# GPS_supply2.net
KiCad netlist of a schematic drawn in Altium Designer
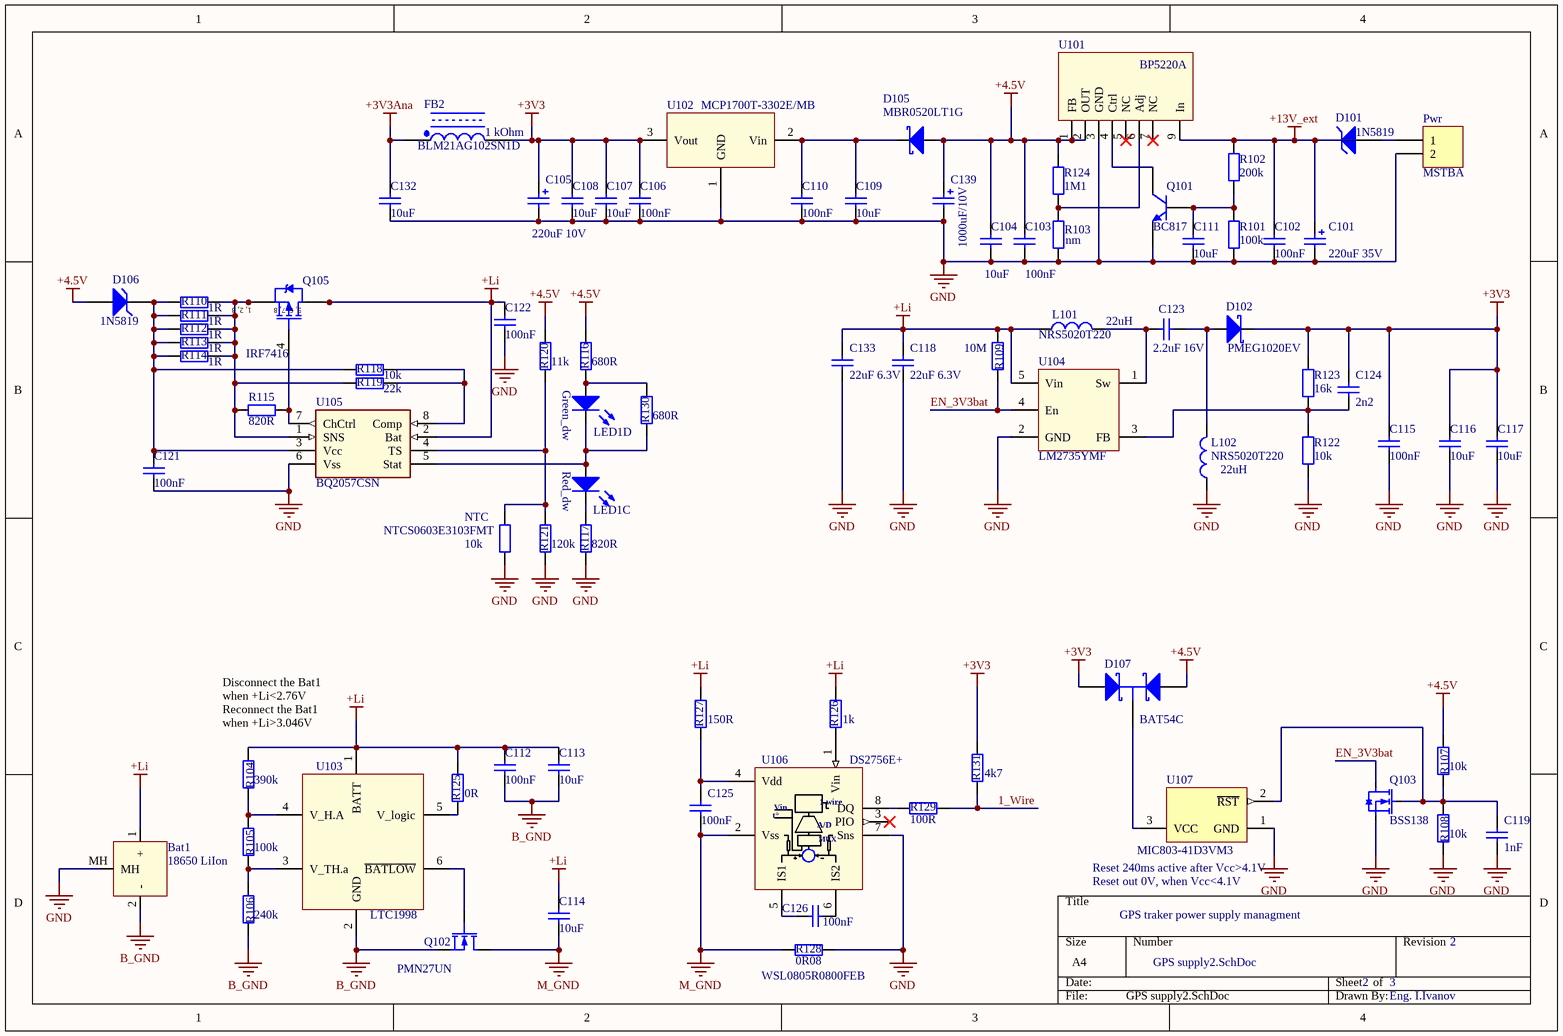
[diagram p0: GPS supply2.SchDoc]

(export (version "E")
  (design (tool "Eeschema 10.0.6"))
  (components
    (comp (ref "Bat1")
      (value "18650 LiIon")
      (footprint "18650")
      (description "18650 cell")
      (fields (field (name "Comment") "LiIon") (field (name "CREATED") "charge"))
      (libsource (lib "ANG_6VA transformers") (part "LiIon"))
    )
    (comp (ref "C101")
      (value "220uF 35V")
      (footprint "Cap electrolyt 7")
      (description "Polarized Capacitor (TH)")
      (fields (field (name "PUBLISHER") "Altium Limited"))
      (libsource (lib "Electolyt Caps") (part "CAP ELECTOLYT"))
    )
    (comp (ref "C102")
      (value "100nF")
      (footprint "2012[0805]")
      (description "Capacitor (Semiconductor SIM Model)")
      (fields (field (name "Comment") "Cap Semi") (field (name "PUBLISHER") "Altium Limited"))
      (libsource (lib "altium-import") (part "root_1_Cap Semi_"))
    )
    (comp (ref "C103")
      (value "100nF")
      (footprint "2012[0805]")
      (description "Capacitor (Semiconductor SIM Model)")
      (fields (field (name "Comment") "Cap Semi") (field (name "PUBLISHER") "Altium Limited"))
      (libsource (lib "Miscellaneous Devices") (part "Cap Semi"))
    )
    (comp (ref "C104")
      (value "10uF")
      (footprint "2012[0805]")
      (description "Capacitor (Semiconductor SIM Model)")
      (fields (field (name "Comment") "Cap Semi") (field (name "PUBLISHER") "Altium Limited"))
      (libsource (lib "Miscellaneous Devices") (part "Cap Semi"))
    )
    (comp (ref "C105")
      (value "220uF 10V")
      (footprint "Cap electrolyt 8")
      (description "Polarized Capacitor (TH)")
      (fields (field (name "Comment") "CAP ELECTOLYT") (field (name "PUBLISHER") "Altium Limited"))
      (libsource (lib "Electolyt Caps") (part "CAP ELECTOLYT"))
    )
    (comp (ref "C106")
      (value "100nF")
      (footprint "2012[0805]")
      (description "Capacitor (Semiconductor SIM Model)")
      (fields (field (name "Comment") "Cap Semi") (field (name "PUBLISHER") "Altium Limited"))
      (libsource (lib "Miscellaneous Devices") (part "Cap Semi"))
    )
    (comp (ref "C107")
      (value "10uF")
      (footprint "2012[0805]")
      (description "Capacitor (Semiconductor SIM Model)")
      (fields (field (name "Comment") "Cap Semi") (field (name "PUBLISHER") "Altium Limited"))
      (libsource (lib "Miscellaneous Devices") (part "Cap Semi"))
    )
    (comp (ref "C108")
      (value "10uF")
      (footprint "2012[0805]")
      (description "Capacitor (Semiconductor SIM Model)")
      (fields (field (name "Comment") "Cap Semi") (field (name "PUBLISHER") "Altium Limited"))
      (libsource (lib "Miscellaneous Devices") (part "Cap Semi"))
    )
    (comp (ref "C109")
      (value "10uF")
      (footprint "2012[0805]")
      (description "Capacitor (Semiconductor SIM Model)")
      (fields (field (name "Comment") "Cap Semi") (field (name "PUBLISHER") "Altium Limited"))
      (libsource (lib "Miscellaneous Devices") (part "Cap Semi"))
    )
    (comp (ref "C110")
      (value "100nF")
      (footprint "2012[0805]")
      (description "Capacitor (Semiconductor SIM Model)")
      (fields (field (name "Comment") "Cap Semi") (field (name "PUBLISHER") "Altium Limited"))
      (libsource (lib "Miscellaneous Devices") (part "Cap Semi"))
    )
    (comp (ref "C111")
      (value "10uF")
      (footprint "2012[0805]")
      (description "Capacitor (Semiconductor SIM Model)")
      (fields (field (name "Comment") "Cap Semi") (field (name "PUBLISHER") "Altium Limited"))
      (libsource (lib "Miscellaneous Devices") (part "Cap Semi"))
    )
    (comp (ref "C112")
      (value "100nF")
      (footprint "2012[0805]")
      (description "Capacitor (Semiconductor SIM Model)")
      (fields (field (name "Comment") "Cap Semi") (field (name "PUBLISHER") "Altium Limited"))
      (libsource (lib "Miscellaneous Devices") (part "Cap Semi"))
    )
    (comp (ref "C113")
      (value "10uF")
      (footprint "2012[0805]")
      (description "Capacitor (Semiconductor SIM Model)")
      (fields (field (name "Comment") "Cap Semi") (field (name "PUBLISHER") "Altium Limited"))
      (libsource (lib "Miscellaneous Devices") (part "Cap Semi"))
    )
    (comp (ref "C114")
      (value "10uF")
      (footprint "2012[0805]")
      (description "Capacitor (Semiconductor SIM Model)")
      (fields (field (name "Comment") "Cap Semi") (field (name "PUBLISHER") "Altium Limited"))
      (libsource (lib "Miscellaneous Devices") (part "Cap Semi"))
    )
    (comp (ref "C115")
      (value "100nF")
      (footprint "2012[0805]")
      (description "Capacitor (Semiconductor SIM Model)")
      (fields (field (name "Comment") "Cap Semi") (field (name "PUBLISHER") "Altium Limited"))
      (libsource (lib "Miscellaneous Devices") (part "Cap Semi"))
    )
    (comp (ref "C116")
      (value "10uF")
      (footprint "2012[0805]")
      (description "Capacitor (Semiconductor SIM Model)")
      (fields (field (name "Comment") "Cap Semi") (field (name "PUBLISHER") "Altium Limited"))
      (libsource (lib "Miscellaneous Devices") (part "Cap Semi"))
    )
    (comp (ref "C117")
      (value "10uF")
      (footprint "2012[0805]")
      (description "Capacitor (Semiconductor SIM Model)")
      (fields (field (name "Comment") "Cap Semi") (field (name "PUBLISHER") "Altium Limited"))
      (libsource (lib "Miscellaneous Devices") (part "Cap Semi"))
    )
    (comp (ref "C118")
      (value "22uF 6.3V")
      (footprint "2012[0805]")
      (description "Capacitor (Semiconductor SIM Model)")
      (fields (field (name "Comment") "Cap Semi") (field (name "PUBLISHER") "Altium Limited"))
      (libsource (lib "Miscellaneous Devices") (part "Cap Semi"))
    )
    (comp (ref "C119")
      (value "1nF")
      (footprint "2012[0805]")
      (description "Capacitor (Semiconductor SIM Model)")
      (fields (field (name "Comment") "Cap Semi") (field (name "PUBLISHER") "Altium Limited"))
      (libsource (lib "Miscellaneous Devices") (part "Cap Semi"))
    )
    (comp (ref "C121")
      (value "100nF")
      (footprint "2012[0805]")
      (description "Capacitor (Semiconductor SIM Model)")
      (fields (field (name "Comment") "Cap Semi") (field (name "PUBLISHER") "Altium Limited"))
      (libsource (lib "Miscellaneous Devices") (part "Cap Semi"))
    )
    (comp (ref "C122")
      (value "100nF")
      (footprint "2012[0805]")
      (description "Capacitor (Semiconductor SIM Model)")
      (fields (field (name "Comment") "Cap Semi") (field (name "PUBLISHER") "Altium Limited"))
      (libsource (lib "Miscellaneous Devices") (part "Cap Semi"))
    )
    (comp (ref "C123")
      (value "2.2uF 16V")
      (footprint "2012[0805]")
      (description "Capacitor (Semiconductor SIM Model)")
      (fields (field (name "Comment") "Cap Semi") (field (name "PUBLISHER") "Altium Limited"))
      (libsource (lib "Miscellaneous Devices") (part "Cap Semi"))
    )
    (comp (ref "C124")
      (value "2n2")
      (footprint "2012[0805]")
      (description "Capacitor (Semiconductor SIM Model)")
      (fields (field (name "Comment") "Cap Semi") (field (name "PUBLISHER") "Altium Limited"))
      (libsource (lib "Miscellaneous Devices") (part "Cap Semi"))
    )
    (comp (ref "C125")
      (value "100nF")
      (footprint "2012[0805]")
      (description "Capacitor (Semiconductor SIM Model)")
      (fields (field (name "Comment") "Cap Semi") (field (name "PUBLISHER") "Altium Limited"))
      (libsource (lib "Miscellaneous Devices") (part "Cap Semi"))
    )
    (comp (ref "C126")
      (value "100nF")
      (footprint "2012[0805]")
      (description "Capacitor (Semiconductor SIM Model)")
      (fields (field (name "Comment") "Cap Semi") (field (name "PUBLISHER") "Altium Limited"))
      (libsource (lib "Miscellaneous Devices") (part "Cap Semi"))
    )
    (comp (ref "C132")
      (value "10uF")
      (footprint "2012[0805]")
      (description "Capacitor (Semiconductor SIM Model)")
      (fields (field (name "Comment") "Cap Semi") (field (name "PUBLISHER") "Altium Limited"))
      (libsource (lib "Miscellaneous Devices") (part "Cap Semi"))
    )
    (comp (ref "C133")
      (value "22uF 6.3V")
      (footprint "2012[0805]")
      (description "Capacitor (Semiconductor SIM Model)")
      (fields (field (name "Comment") "Cap Semi") (field (name "PUBLISHER") "Altium Limited"))
      (libsource (lib "Miscellaneous Devices") (part "Cap Semi"))
    )
    (comp (ref "C139")
      (value "1000uF/10V")
      (footprint "Cap electrolyt 7")
      (description "Polarized Capacitor (TH)")
      (fields (field (name "Comment") "CAP ELECTOLYT") (field (name "PUBLISHER") "Altium Limited"))
      (libsource (lib "Electolyt Caps") (part "CAP ELECTOLYT"))
    )
    (comp (ref "D101")
      (value "1N5819")
      (footprint "DO214")
      (description "Silicon Zener Diode (3W)")
      (fields (field (name "PUBLISHER") "Altium Limited"))
      (libsource (lib "Vishay Telefunken Discrete Diode") (part "BZG05C4V7"))
    )
    (comp (ref "D102")
      (value "PMEG1020EV")
      (footprint "SOT-666-DIODE")
      (description "Ultra low VF MEGA Schottky barrier  rectifier")
      (libsource (lib "ANG_6VA transformers") (part "PMEG1020EV"))
    )
    (comp (ref "D105")
      (value "MBR0520LT1G")
      (footprint "SOD-123")
      (description "DIODE, SCHOTTKY, 0.5A, 20V, 0.38V@0.5A")
      (fields (field (name "MANUFACTURER") "On Semiconductor") (field (name "CREATED BY") "Charge"))
      (libsource (lib "ANG_6VA transformers") (part "MBR0520LT1G"))
    )
    (comp (ref "D106")
      (value "1N5819")
      (footprint "DO214")
      (description "Silicon Zener Diode (3W)")
      (fields (field (name "PUBLISHER") "Altium Limited"))
      (libsource (lib "Vishay Telefunken Discrete Diode") (part "BZG05C4V7"))
    )
    (comp (ref "D107")
      (value "BAT54C")
      (footprint "SOT23_N")
      (description "Schottky Barrier Double Diode")
      (fields (field (name "PUBLISHER") "Altium Limited"))
      (libsource (lib "Philips Discrete Diode - Schottky") (part "BAT54C"))
    )
    (comp (ref "FB2")
      (value "BLM21AG102SN1D")
      (footprint "RESC2012N")
      (description "Isolated Inductor")
      (fields (field (name "ALTIUM_VALUE") "1 kOhm") (field (name "PUBLISHER") "Altium Limited"))
      (libsource (lib "Miscellaneous Devices") (part "Inductor Isolated"))
    )
    (comp (ref "L101")
      (value "NRS5020T220")
      (footprint "NRS5020Txxx")
      (fields (field (name "INDUCTANCE") "22uH") (field (name "Comment") "NRS5020T Taiyo-Yuden inductor"))
      (libsource (lib "Inductors") (part "NRS5020T Taiyo-Yuden inductor"))
    )
    (comp (ref "L102")
      (value "NRS5020T220")
      (footprint "NRS5020Txxx")
      (fields (field (name "INDUCTANCE") "22uH") (field (name "Comment") "NRS5020T Taiyo-Yuden inductor"))
      (libsource (lib "Inductors") (part "NRS5020T Taiyo-Yuden inductor"))
    )
    (comp (ref "LED1")
      (value "4x LED's")
      (footprint "515-1061F_2x dual LED's")
      (libsource (lib "ANG_6VA transformers") (part "515-1061F_2x dual LED's"))
    )
    (comp (ref "NTC")
      (value "10k")
      (footprint "1608[0603]")
      (description "Resistor")
      (fields (field (name "Comment") "Res2") (field (name "PUBLISHER") "Altium Limited"))
      (libsource (lib "Miscellaneous Devices") (part "Res2"))
    )
    (comp (ref "Pwr")
      (value "MSTBA")
      (footprint "MSTBA2.5/2-G-5.08")
      (description "Header, 2-Pin")
      (fields (field (name "PUBLISHER") "Altium Limited"))
      (libsource (lib "*") (part "TS-501 2P"))
    )
    (comp (ref "Q101")
      (value "BC817")
      (footprint "SOT23_N")
      (description "NPN General-purpose Transistor")
      (fields (field (name "PUBLISHER") "Altium Limited"))
      (libsource (lib "Philips Discrete BJT - Low Power") (part "BC817"))
    )
    (comp (ref "Q102")
      (value "PMN27UN")
      (footprint "SOT-23-6-MOSFET")
      (description "NMOSFET 20V, 5A, Ugs_th=0.7V, Rds=40mOhms")
      (fields (field (name "Comment") "TrenchMOS™ ultra low level FET"))
      (libsource (lib "ANG_6VA transformers") (part "PMN27UN"))
    )
    (comp (ref "Q103")
      (value "BSS138")
      (footprint "SOT-23_my")
      (fields (field (name "Comment") "My BSS138"))
      (libsource (lib "ANG_6VA transformers") (part "BSS138_my"))
    )
    (comp (ref "Q105")
      (value "IRF7416")
      (footprint "SO-8_N")
      (description "HEXFET Power MOSFET")
      (fields (field (name "PUBLISHER") "Altium Limited"))
      (libsource (lib "IR Discrete MOSFET - Power") (part "IRF7416"))
    )
    (comp (ref "R101")
      (value "100k")
      (footprint "2012[0805]")
      (description "Resistor")
      (fields (field (name "Comment") "Res2") (field (name "PUBLISHER") "Altium Limited"))
      (libsource (lib "") (part "Res2_1"))
    )
    (comp (ref "R102")
      (value "200k")
      (footprint "2012[0805]")
      (description "Resistor")
      (fields (field (name "Comment") "Res2") (field (name "PUBLISHER") "Altium Limited"))
      (libsource (lib "") (part "Res2_1"))
    )
    (comp (ref "R103")
      (value "nm")
      (footprint "2012[0805]")
      (description "Resistor")
      (fields (field (name "Comment") "Res2") (field (name "PUBLISHER") "Altium Limited"))
      (libsource (lib "") (part "Res2_1"))
    )
    (comp (ref "R104")
      (value "390k")
      (footprint "2012[0805]")
      (description "Resistor")
      (fields (field (name "Comment") "Res2") (field (name "PUBLISHER") "Altium Limited"))
      (libsource (lib "") (part "Res2_1"))
    )
    (comp (ref "R105")
      (value "100k")
      (footprint "2012[0805]")
      (description "Resistor")
      (fields (field (name "Comment") "Res2") (field (name "PUBLISHER") "Altium Limited"))
      (libsource (lib "") (part "Res2_1"))
    )
    (comp (ref "R106")
      (value "240k")
      (footprint "2012[0805]")
      (description "Resistor")
      (fields (field (name "Comment") "Res2") (field (name "PUBLISHER") "Altium Limited"))
      (libsource (lib "") (part "Res2_1"))
    )
    (comp (ref "R107")
      (value "10k")
      (footprint "2012[0805]")
      (description "Resistor")
      (fields (field (name "Comment") "Res2") (field (name "PUBLISHER") "Altium Limited"))
      (libsource (lib "") (part "Res2_1"))
    )
    (comp (ref "R108")
      (value "10k")
      (footprint "2012[0805]")
      (description "Resistor")
      (fields (field (name "Comment") "Res2") (field (name "PUBLISHER") "Altium Limited"))
      (libsource (lib "") (part "Res2_1"))
    )
    (comp (ref "R109")
      (value "10M")
      (footprint "2012[0805]")
      (description "Resistor")
      (fields (field (name "Comment") "Res2") (field (name "PUBLISHER") "Altium Limited"))
      (libsource (lib "") (part "Res2_1"))
    )
    (comp (ref "R110")
      (value "1R")
      (footprint "2012[0805]")
      (description "Resistor")
      (fields (field (name "Comment") "Res2") (field (name "PUBLISHER") "Altium Limited"))
      (libsource (lib "") (part "Res2_3"))
    )
    (comp (ref "R111")
      (value "1R")
      (footprint "2012[0805]")
      (description "Resistor")
      (fields (field (name "Comment") "Res2") (field (name "PUBLISHER") "Altium Limited"))
      (libsource (lib "") (part "Res2_3"))
    )
    (comp (ref "R112")
      (value "1R")
      (footprint "2012[0805]")
      (description "Resistor")
      (fields (field (name "Comment") "Res2") (field (name "PUBLISHER") "Altium Limited"))
      (libsource (lib "") (part "Res2_3"))
    )
    (comp (ref "R113")
      (value "1R")
      (footprint "2012[0805]")
      (description "Resistor")
      (fields (field (name "Comment") "Res2") (field (name "PUBLISHER") "Altium Limited"))
      (libsource (lib "") (part "Res2_3"))
    )
    (comp (ref "R114")
      (value "1R")
      (footprint "2012[0805]")
      (description "Resistor")
      (fields (field (name "Comment") "Res2") (field (name "PUBLISHER") "Altium Limited"))
      (libsource (lib "") (part "Res2_3"))
    )
    (comp (ref "R115")
      (value "820R")
      (footprint "2012[0805]")
      (description "Resistor")
      (fields (field (name "Comment") "Res2") (field (name "PUBLISHER") "Altium Limited"))
      (libsource (lib "") (part "Res2_2"))
    )
    (comp (ref "R116")
      (value "680R")
      (footprint "2012[0805]")
      (description "Resistor")
      (fields (field (name "Comment") "Res2") (field (name "PUBLISHER") "Altium Limited"))
      (libsource (lib "") (part "Res2_1"))
    )
    (comp (ref "R117")
      (value "820R")
      (footprint "2012[0805]")
      (description "Resistor")
      (fields (field (name "Comment") "Res2") (field (name "PUBLISHER") "Altium Limited"))
      (libsource (lib "") (part "Res2_1"))
    )
    (comp (ref "R118")
      (value "10k")
      (footprint "2012[0805]")
      (description "Resistor")
      (fields (field (name "Comment") "Res2") (field (name "PUBLISHER") "Altium Limited"))
      (libsource (lib "") (part "Res2_3"))
    )
    (comp (ref "R119")
      (value "22k")
      (footprint "2012[0805]")
      (description "Resistor")
      (fields (field (name "Comment") "Res2") (field (name "PUBLISHER") "Altium Limited"))
      (libsource (lib "") (part "Res2_3"))
    )
    (comp (ref "R120")
      (value "11k")
      (footprint "2012[0805]")
      (description "Resistor")
      (fields (field (name "Comment") "Res2") (field (name "PUBLISHER") "Altium Limited"))
      (libsource (lib "Miscellaneous Devices") (part "Res2"))
    )
    (comp (ref "R121")
      (value "120k")
      (footprint "2012[0805]")
      (description "Resistor")
      (fields (field (name "Comment") "Res2") (field (name "PUBLISHER") "Altium Limited"))
      (libsource (lib "Miscellaneous Devices") (part "Res2"))
    )
    (comp (ref "R122")
      (value "10k")
      (footprint "2012[0805]")
      (description "Resistor")
      (fields (field (name "Comment") "Res2") (field (name "PUBLISHER") "Altium Limited"))
      (libsource (lib "Miscellaneous Devices") (part "Res2"))
    )
    (comp (ref "R123")
      (value "16k")
      (footprint "2012[0805]")
      (description "Resistor")
      (fields (field (name "Comment") "Res2") (field (name "PUBLISHER") "Altium Limited"))
      (libsource (lib "Miscellaneous Devices") (part "Res2"))
    )
    (comp (ref "R124")
      (value "1M1")
      (footprint "2012[0805]")
      (description "Resistor")
      (fields (field (name "Comment") "Res2") (field (name "PUBLISHER") "Altium Limited"))
      (libsource (lib "Miscellaneous Devices") (part "Res2"))
    )
    (comp (ref "R125")
      (value "0R")
      (footprint "2012[0805]")
      (description "Resistor")
      (fields (field (name "Comment") "Res2") (field (name "PUBLISHER") "Altium Limited"))
      (libsource (lib "Miscellaneous Devices") (part "Res2"))
    )
    (comp (ref "R126")
      (value "1k")
      (footprint "2012[0805]")
      (description "Resistor")
      (fields (field (name "Comment") "Res2") (field (name "PUBLISHER") "Altium Limited"))
      (libsource (lib "Miscellaneous Devices") (part "Res2"))
    )
    (comp (ref "R127")
      (value "150R")
      (footprint "2012[0805]")
      (description "Resistor")
      (fields (field (name "Comment") "Res2") (field (name "PUBLISHER") "Altium Limited"))
      (libsource (lib "Miscellaneous Devices") (part "Res2"))
    )
    (comp (ref "R128")
      (value "WSL0805R0800FEB")
      (footprint "2012[0805]")
      (description "Resistor")
      (fields (field (name "ALTIUM_VALUE") "0R08") (field (name "PUBLISHER") "Altium Limited"))
      (libsource (lib "") (part "Res2_2"))
    )
    (comp (ref "R129")
      (value "100R")
      (footprint "2012[0805]")
      (description "Resistor")
      (fields (field (name "Comment") "Res2") (field (name "PUBLISHER") "Altium Limited"))
      (libsource (lib "") (part "Res2_2"))
    )
    (comp (ref "R130")
      (value "680R")
      (footprint "2012[0805]")
      (description "Resistor")
      (fields (field (name "Comment") "Res2") (field (name "PUBLISHER") "Altium Limited"))
      (libsource (lib "") (part "Res2_1"))
    )
    (comp (ref "R131")
      (value "4k7")
      (footprint "2012[0805]")
      (description "Resistor")
      (fields (field (name "Comment") "Res2") (field (name "PUBLISHER") "Altium Limited"))
      (libsource (lib "") (part "Res2_1"))
    )
    (comp (ref "U101")
      (value "BP5220A")
      (footprint "BP502xA")
      (description "Rohm switching DC/DC regulator")
      (fields (field (name "CREATED") "charge"))
      (libsource (lib "ANG_6VA transformers") (part "BP502x_Rohm"))
    )
    (comp (ref "U102")
      (value "MCP1700T-3302E/MB")
      (footprint "SOT89_my")
      (fields (field (name "Comment") "MCP1700T-xxxx"))
      (libsource (lib "*") (part "MCP1700T-xxxx"))
    )
    (comp (ref "U103")
      (value "LTC1998")
      (footprint "SOT26A-6N")
      (description "2.5uA, 1% Accurate  SOT-23 Comparator and Voltage  Reference for Battery Monitoring")
      (fields
        (field (name "Comment") "2.5?A, 1% Accurate  SOT-23 Comparator and Voltage  Reference for Battery Monitoring")
      )
      (libsource (lib "ANG_6VA transformers") (part "LTC1998"))
    )
    (comp (ref "U104")
      (value "LM2735YMF")
      (footprint "SOT23-5AN")
      (fields (field (name "Comment") "520kHz Space-Efficient Boost and SEPIC DC-DC  Regulator"))
      (libsource (lib "ANG_6VA transformers") (part "LM2735YMF"))
    )
    (comp (ref "U105")
      (value "BQ2057CSN")
      (footprint "SO8")
      (description "Advanced charge controller IC")
      (libsource (lib "ANG_6VA transformers") (part "BQ2057CSN"))
    )
    (comp (ref "U106")
      (value "DS2756E+")
      (footprint "TSSOP 8_My")
      (description "high-precision battery fuel gauge")
      (fields
        (field (name "MANUFACTURER") "Dallas/Maxim Integrated")
        (field (name "Comment") "1 wire fuel gauge")
      )
      (libsource (lib "ANG_6VA transformers") (part "DS2756+"))
    )
    (comp (ref "U107")
      (value "MIC803-41D3VM3")
      (footprint "MF03A_N")
      (description "3-Pin Microprocessor Reset Circuit, 4.00V Threshold")
      (fields
        (field (name "PARTNUMBER") "LM809M3-4.00")
        (field (name "MANUFACTURER") "National Semiconductor")
        (field (name "PUBLISHER") "Altium Limited")
      )
      (libsource (lib "NSC MiscPower") (part "LM809M3-4.00"))
    )
  )
  (nets
    (net (code "1") (name "+3V3") (class "Default")
      (node (ref "C105") (pin "1") (pinfunction "1_1") (pintype "passive"))
      (node (ref "C106") (pin "2") (pinfunction "2_2") (pintype "passive"))
      (node (ref "C107") (pin "2") (pinfunction "2_2") (pintype "passive"))
      (node (ref "C108") (pin "2") (pinfunction "2_2") (pintype "passive"))
      (node (ref "C115") (pin "2") (pinfunction "2_2") (pintype "passive"))
      (node (ref "C116") (pin "2") (pinfunction "2_2") (pintype "passive"))
      (node (ref "C117") (pin "2") (pinfunction "2_2") (pintype "passive"))
      (node (ref "C124") (pin "2") (pinfunction "2_2") (pintype "passive"))
      (node (ref "D102") (pin "2") (pinfunction "K_2") (pintype "passive"))
      (node (ref "D107") (pin "2") (pinfunction "A2_2") (pintype "passive"))
      (node (ref "FB2") (pin "2") (pinfunction "2_2") (pintype "passive"))
      (node (ref "R123") (pin "1") (pinfunction "1_1") (pintype "passive"))
      (node (ref "R131") (pin "2") (pinfunction "2_2") (pintype "passive"))
      (node (ref "U102") (pin "3") (pinfunction "Vout_3") (pintype "passive"))
    )
    (net (code "2") (name "+3V3Ana") (class "Default")
      (node (ref "C132") (pin "2") (pinfunction "2_2") (pintype "passive"))
      (node (ref "FB2") (pin "1") (pinfunction "1_1") (pintype "passive"))
    )
    (net (code "3") (name "+4.5V") (class "Default")
      (node (ref "C103") (pin "2") (pinfunction "2_2") (pintype "passive"))
      (node (ref "C104") (pin "2") (pinfunction "2_2") (pintype "passive"))
      (node (ref "C139") (pin "1") (pinfunction "1_1") (pintype "passive"))
      (node (ref "D105") (pin "1") (pinfunction "A_1") (pintype "passive"))
      (node (ref "D106") (pin "1") (pinfunction "A_1") (pintype "passive"))
      (node (ref "D107") (pin "1") (pinfunction "A1_1") (pintype "passive"))
      (node (ref "R107") (pin "2") (pinfunction "2_2") (pintype "passive"))
      (node (ref "R116") (pin "2") (pinfunction "2_2") (pintype "passive"))
      (node (ref "R120") (pin "1") (pinfunction "1_1") (pintype "passive"))
      (node (ref "R124") (pin "1") (pinfunction "1_1") (pintype "passive"))
      (node (ref "U101") (pin "1") (pinfunction "FB_1") (pintype "passive"))
      (node (ref "U101") (pin "2") (pinfunction "OUT_2") (pintype "power_in"))
    )
    (net (code "4") (name "+13V_ext") (class "Default")
      (node (ref "C101") (pin "1") (pinfunction "1_1") (pintype "passive"))
      (node (ref "C102") (pin "2") (pinfunction "2_2") (pintype "passive"))
      (node (ref "D101") (pin "2") (pinfunction "K_2") (pintype "passive"))
      (node (ref "R102") (pin "2") (pinfunction "2_2") (pintype "passive"))
      (node (ref "U101") (pin "9") (pinfunction "In_9") (pintype "passive"))
    )
    (net (code "5") (name "+Li") (class "Default")
      (node (ref "Bat1") (pin "1") (pinfunction "+_1") (pintype "passive"))
      (node (ref "C112") (pin "2") (pinfunction "2_2") (pintype "passive"))
      (node (ref "C113") (pin "2") (pinfunction "2_2") (pintype "passive"))
      (node (ref "C114") (pin "2") (pinfunction "2_2") (pintype "passive"))
      (node (ref "C118") (pin "2") (pinfunction "2_2") (pintype "passive"))
      (node (ref "C122") (pin "2") (pinfunction "2_2") (pintype "passive"))
      (node (ref "C133") (pin "2") (pinfunction "2_2") (pintype "passive"))
      (node (ref "L101") (pin "1") (pinfunction "1_1") (pintype "passive"))
      (node (ref "Q105") (pin "5") (pinfunction "D_5") (pintype "passive"))
      (node (ref "Q105") (pin "6") (pinfunction "D_6") (pintype "passive"))
      (node (ref "Q105") (pin "7") (pinfunction "D_7") (pintype "passive"))
      (node (ref "Q105") (pin "8") (pinfunction "D_8") (pintype "passive"))
      (node (ref "R104") (pin "2") (pinfunction "2_2") (pintype "passive"))
      (node (ref "R109") (pin "2") (pinfunction "2_2") (pintype "passive"))
      (node (ref "R125") (pin "1") (pinfunction "1_1") (pintype "passive"))
      (node (ref "R126") (pin "1") (pinfunction "1_1") (pintype "passive"))
      (node (ref "R127") (pin "1") (pinfunction "1_1") (pintype "passive"))
      (node (ref "U103") (pin "1") (pinfunction "BATT_1") (pintype "passive"))
      (node (ref "U104") (pin "5") (pinfunction "Vin_5") (pintype "passive"))
      (node (ref "U105") (pin "2") (pinfunction "Bat_2") (pintype "input"))
    )
    (net (code "6") (name "/1_Wire") (class "Default")
      (node (ref "R129") (pin "2") (pinfunction "2_2") (pintype "passive"))
      (node (ref "R131") (pin "1") (pinfunction "1_1") (pintype "passive"))
    )
    (net (code "7") (name "/EN_3V3bat") (class "Default")
      (node (ref "Q103") (pin "3") (pinfunction "D_3") (pintype "passive"))
      (node (ref "R109") (pin "1") (pinfunction "1_1") (pintype "passive"))
      (node (ref "U104") (pin "4") (pinfunction "En_4") (pintype "passive"))
    )
    (net (code "8") (name "B_GND") (class "Default")
      (node (ref "Bat1") (pin "2") (pinfunction "-_2") (pintype "passive"))
      (node (ref "C112") (pin "1") (pinfunction "1_1") (pintype "passive"))
      (node (ref "C113") (pin "1") (pinfunction "1_1") (pintype "passive"))
      (node (ref "Q102") (pin "3") (pinfunction "S_3") (pintype "passive"))
      (node (ref "R106") (pin "1") (pinfunction "1_1") (pintype "passive"))
      (node (ref "U103") (pin "2") (pinfunction "GND_2") (pintype "passive"))
    )
    (net (code "9") (name "GND") (class "Default")
      (node (ref "Bat1") (pin "MH") (pinfunction "MH_MH") (pintype "passive"))
      (node (ref "C101") (pin "2") (pinfunction "2_2") (pintype "passive"))
      (node (ref "C102") (pin "1") (pinfunction "1_1") (pintype "passive"))
      (node (ref "C103") (pin "1") (pinfunction "1_1") (pintype "passive"))
      (node (ref "C104") (pin "1") (pinfunction "1_1") (pintype "passive"))
      (node (ref "C105") (pin "2") (pinfunction "2_2") (pintype "passive"))
      (node (ref "C106") (pin "1") (pinfunction "1_1") (pintype "passive"))
      (node (ref "C107") (pin "1") (pinfunction "1_1") (pintype "passive"))
      (node (ref "C108") (pin "1") (pinfunction "1_1") (pintype "passive"))
      (node (ref "C109") (pin "1") (pinfunction "1_1") (pintype "passive"))
      (node (ref "C110") (pin "1") (pinfunction "1_1") (pintype "passive"))
      (node (ref "C111") (pin "1") (pinfunction "1_1") (pintype "passive"))
      (node (ref "C115") (pin "1") (pinfunction "1_1") (pintype "passive"))
      (node (ref "C116") (pin "1") (pinfunction "1_1") (pintype "passive"))
      (node (ref "C117") (pin "1") (pinfunction "1_1") (pintype "passive"))
      (node (ref "C118") (pin "1") (pinfunction "1_1") (pintype "passive"))
      (node (ref "C119") (pin "1") (pinfunction "1_1") (pintype "passive"))
      (node (ref "C121") (pin "1") (pinfunction "1_1") (pintype "passive"))
      (node (ref "C122") (pin "1") (pinfunction "1_1") (pintype "passive"))
      (node (ref "C132") (pin "1") (pinfunction "1_1") (pintype "passive"))
      (node (ref "C133") (pin "1") (pinfunction "1_1") (pintype "passive"))
      (node (ref "C139") (pin "2") (pinfunction "2_2") (pintype "passive"))
      (node (ref "L102") (pin "1") (pinfunction "1_1") (pintype "passive"))
      (node (ref "NTC") (pin "2") (pinfunction "2_2") (pintype "passive"))
      (node (ref "Pwr") (pin "2") (pinfunction "2_2") (pintype "passive"))
      (node (ref "Q101") (pin "2") (pinfunction "E_2") (pintype "passive"))
      (node (ref "Q103") (pin "2") (pinfunction "S_2") (pintype "passive"))
      (node (ref "R101") (pin "1") (pinfunction "1_1") (pintype "passive"))
      (node (ref "R103") (pin "1") (pinfunction "1_1") (pintype "passive"))
      (node (ref "R108") (pin "1") (pinfunction "1_1") (pintype "passive"))
      (node (ref "R117") (pin "1") (pinfunction "1_1") (pintype "passive"))
      (node (ref "R121") (pin "2") (pinfunction "2_2") (pintype "passive"))
      (node (ref "R122") (pin "2") (pinfunction "2_2") (pintype "passive"))
      (node (ref "R128") (pin "2") (pinfunction "2_2") (pintype "passive"))
      (node (ref "U101") (pin "3") (pinfunction "GND_3") (pintype "power_in"))
      (node (ref "U102") (pin "1") (pinfunction "GND_1") (pintype "passive"))
      (node (ref "U104") (pin "2") (pinfunction "GND_2") (pintype "passive"))
      (node (ref "U105") (pin "6") (pinfunction "Vss_6") (pintype "power_in"))
      (node (ref "U106") (pin "7") (pinfunction "Sns_7") (pintype "passive"))
      (node (ref "U107") (pin "1") (pinfunction "GND_1") (pintype "power_in"))
    )
    (net (code "10") (name "M_GND") (class "Default")
      (node (ref "C114") (pin "1") (pinfunction "1_1") (pintype "passive"))
      (node (ref "C125") (pin "1") (pinfunction "1_1") (pintype "passive"))
      (node (ref "Q102") (pin "1") (pinfunction "D_1") (pintype "passive"))
      (node (ref "R128") (pin "1") (pinfunction "1_1") (pintype "passive"))
      (node (ref "U106") (pin "2") (pinfunction "Vss_2") (pintype "power_in"))
    )
    (net (code "11") (name "Net-(D101-A)") (class "Default")
      (node (ref "D101") (pin "1") (pinfunction "A_1") (pintype "passive"))
      (node (ref "Pwr") (pin "1") (pinfunction "1_1") (pintype "passive"))
    )
    (net (code "12") (name "Net-(D102-A)") (class "Default")
      (node (ref "C123") (pin "1") (pinfunction "1_1") (pintype "passive"))
      (node (ref "D102") (pin "1") (pinfunction "A_1") (pintype "passive"))
      (node (ref "L102") (pin "2") (pinfunction "2_2") (pintype "passive"))
    )
    (net (code "13") (name "Net-(D105-K)") (class "Default")
      (node (ref "C109") (pin "2") (pinfunction "2_2") (pintype "passive"))
      (node (ref "C110") (pin "2") (pinfunction "2_2") (pintype "passive"))
      (node (ref "D105") (pin "2") (pinfunction "K_2") (pintype "passive"))
      (node (ref "U102") (pin "2") (pinfunction "Vin_2") (pintype "passive"))
    )
    (net (code "14") (name "Net-(D106-K)") (class "Default")
      (node (ref "C121") (pin "2") (pinfunction "2_2") (pintype "passive"))
      (node (ref "D106") (pin "2") (pinfunction "K_2") (pintype "passive"))
      (node (ref "R110") (pin "2") (pinfunction "2_2") (pintype "passive"))
      (node (ref "R111") (pin "2") (pinfunction "2_2") (pintype "passive"))
      (node (ref "R112") (pin "2") (pinfunction "2_2") (pintype "passive"))
      (node (ref "R113") (pin "2") (pinfunction "2_2") (pintype "passive"))
      (node (ref "R114") (pin "2") (pinfunction "2_2") (pintype "passive"))
      (node (ref "R118") (pin "2") (pinfunction "2_2") (pintype "passive"))
      (node (ref "U105") (pin "3") (pinfunction "Vcc_3") (pintype "power_in"))
    )
    (net (code "15") (name "Net-(D107-K)") (class "Default")
      (node (ref "D107") (pin "3") (pinfunction "K_3") (pintype "passive"))
      (node (ref "U107") (pin "3") (pinfunction "VCC_3") (pintype "power_in"))
    )
    (net (code "16") (name "Net-(LED1C-A)") (class "Default")
      (node (ref "LED1") (pin "2d") (pinfunction "A_2d") (pintype "passive"))
      (node (ref "LED1") (pin "3d") (pinfunction "K_3d") (pintype "passive"))
      (node (ref "R130") (pin "1") (pinfunction "1_1") (pintype "passive"))
      (node (ref "U105") (pin "5") (pinfunction "Stat_5") (pintype "passive"))
    )
    (net (code "17") (name "Net-(LED1C-K)") (class "Default")
      (node (ref "LED1") (pin "1d") (pinfunction "K_1d") (pintype "passive"))
      (node (ref "R117") (pin "2") (pinfunction "2_2") (pintype "passive"))
    )
    (net (code "18") (name "Net-(LED1D-A)") (class "Default")
      (node (ref "LED1") (pin "4d") (pinfunction "A_4d") (pintype "passive"))
      (node (ref "R116") (pin "1") (pinfunction "1_1") (pintype "passive"))
      (node (ref "R130") (pin "2") (pinfunction "2_2") (pintype "passive"))
    )
    (net (code "19") (name "Net-(Q101-B)") (class "Default")
      (node (ref "C111") (pin "2") (pinfunction "2_2") (pintype "passive"))
      (node (ref "Q101") (pin "1") (pinfunction "B_1") (pintype "passive"))
      (node (ref "R101") (pin "2") (pinfunction "2_2") (pintype "passive"))
      (node (ref "R102") (pin "1") (pinfunction "1_1") (pintype "passive"))
    )
    (net (code "20") (name "Net-(Q101-C)") (class "Default")
      (node (ref "Q101") (pin "3") (pinfunction "C_3") (pintype "passive"))
      (node (ref "U101") (pin "4") (pinfunction "Ctrl_4") (pintype "passive"))
    )
    (net (code "21") (name "Net-(Q102-G)") (class "Default")
      (node (ref "Q102") (pin "2") (pinfunction "G_2") (pintype "passive"))
      (node (ref "U103") (pin "6") (pinfunction "~{BATLOW}_6") (pintype "open_collector"))
    )
    (net (code "22") (name "Net-(Q103-G)") (class "Default")
      (node (ref "C119") (pin "2") (pinfunction "2_2") (pintype "passive"))
      (node (ref "Q103") (pin "1") (pinfunction "G_1") (pintype "passive"))
      (node (ref "R107") (pin "1") (pinfunction "1_1") (pintype "passive"))
      (node (ref "R108") (pin "2") (pinfunction "2_2") (pintype "passive"))
      (node (ref "U107") (pin "2") (pinfunction "~{RST}_2") (pintype "output"))
    )
    (net (code "23") (name "Net-(Q105-G)") (class "Default")
      (node (ref "Q105") (pin "4") (pinfunction "G_4") (pintype "passive"))
      (node (ref "R115") (pin "2") (pinfunction "2_2") (pintype "passive"))
      (node (ref "U105") (pin "7") (pinfunction "ChCtrl_7") (pintype "output"))
    )
    (net (code "24") (name "Net-(U101-Adj)") (class "Default")
      (node (ref "R103") (pin "2") (pinfunction "2_2") (pintype "passive"))
      (node (ref "R124") (pin "2") (pinfunction "2_2") (pintype "passive"))
      (node (ref "U101") (pin "6") (pinfunction "Adj_6") (pintype "passive"))
    )
    (net (code "25") (name "Net-(U103-V_H.A)") (class "Default")
      (node (ref "R104") (pin "1") (pinfunction "1_1") (pintype "passive"))
      (node (ref "R105") (pin "2") (pinfunction "2_2") (pintype "passive"))
      (node (ref "U103") (pin "4") (pinfunction "V_H.A_4") (pintype "passive"))
    )
    (net (code "26") (name "Net-(U103-V_TH.a)") (class "Default")
      (node (ref "R105") (pin "1") (pinfunction "1_1") (pintype "passive"))
      (node (ref "R106") (pin "2") (pinfunction "2_2") (pintype "passive"))
      (node (ref "U103") (pin "3") (pinfunction "V_TH.a_3") (pintype "passive"))
    )
    (net (code "27") (name "Net-(U103-V_logic)") (class "Default")
      (node (ref "R125") (pin "2") (pinfunction "2_2") (pintype "passive"))
      (node (ref "U103") (pin "5") (pinfunction "V_logic_5") (pintype "passive"))
    )
    (net (code "28") (name "Net-(U104-FB)") (class "Default")
      (node (ref "C124") (pin "1") (pinfunction "1_1") (pintype "passive"))
      (node (ref "R122") (pin "1") (pinfunction "1_1") (pintype "passive"))
      (node (ref "R123") (pin "2") (pinfunction "2_2") (pintype "passive"))
      (node (ref "U104") (pin "3") (pinfunction "FB_3") (pintype "passive"))
    )
    (net (code "29") (name "Net-(U104-Sw)") (class "Default")
      (node (ref "C123") (pin "2") (pinfunction "2_2") (pintype "passive"))
      (node (ref "L101") (pin "2") (pinfunction "2_2") (pintype "passive"))
      (node (ref "U104") (pin "1") (pinfunction "Sw_1") (pintype "passive"))
    )
    (net (code "30") (name "Net-(U105-Comp)") (class "Default")
      (node (ref "R118") (pin "1") (pinfunction "1_1") (pintype "passive"))
      (node (ref "R119") (pin "1") (pinfunction "1_1") (pintype "passive"))
      (node (ref "U105") (pin "8") (pinfunction "Comp_8") (pintype "input"))
    )
    (net (code "31") (name "Net-(U105-SNS)") (class "Default")
      (node (ref "Q105") (pin "1") (pinfunction "S_1") (pintype "passive"))
      (node (ref "Q105") (pin "2") (pinfunction "S_2") (pintype "passive"))
      (node (ref "Q105") (pin "3") (pinfunction "S_3") (pintype "passive"))
      (node (ref "R110") (pin "1") (pinfunction "1_1") (pintype "passive"))
      (node (ref "R111") (pin "1") (pinfunction "1_1") (pintype "passive"))
      (node (ref "R112") (pin "1") (pinfunction "1_1") (pintype "passive"))
      (node (ref "R113") (pin "1") (pinfunction "1_1") (pintype "passive"))
      (node (ref "R114") (pin "1") (pinfunction "1_1") (pintype "passive"))
      (node (ref "R115") (pin "1") (pinfunction "1_1") (pintype "passive"))
      (node (ref "R119") (pin "2") (pinfunction "2_2") (pintype "passive"))
      (node (ref "U105") (pin "1") (pinfunction "SNS_1") (pintype "input"))
    )
    (net (code "32") (name "Net-(U105-TS)") (class "Default")
      (node (ref "NTC") (pin "1") (pinfunction "1_1") (pintype "passive"))
      (node (ref "R120") (pin "2") (pinfunction "2_2") (pintype "passive"))
      (node (ref "R121") (pin "1") (pinfunction "1_1") (pintype "passive"))
      (node (ref "U105") (pin "4") (pinfunction "TS_4") (pintype "passive"))
    )
    (net (code "33") (name "Net-(U106-DQ)") (class "Default")
      (node (ref "R129") (pin "1") (pinfunction "1_1") (pintype "passive"))
      (node (ref "U106") (pin "8") (pinfunction "DQ_8") (pintype "open_collector"))
    )
    (net (code "34") (name "Net-(U106-IS1)") (class "Default")
      (node (ref "C126") (pin "2") (pinfunction "2_2") (pintype "passive"))
      (node (ref "U106") (pin "5") (pinfunction "IS1_5") (pintype "passive"))
    )
    (net (code "35") (name "Net-(U106-IS2)") (class "Default")
      (node (ref "C126") (pin "1") (pinfunction "1_1") (pintype "passive"))
      (node (ref "U106") (pin "6") (pinfunction "IS2_6") (pintype "passive"))
    )
    (net (code "36") (name "Net-(U106-Vdd)") (class "Default")
      (node (ref "C125") (pin "2") (pinfunction "2_2") (pintype "passive"))
      (node (ref "R127") (pin "2") (pinfunction "2_2") (pintype "passive"))
      (node (ref "U106") (pin "4") (pinfunction "Vdd_4") (pintype "power_in"))
    )
    (net (code "37") (name "Net-(U106-Vin)") (class "Default")
      (node (ref "R126") (pin "2") (pinfunction "2_2") (pintype "passive"))
      (node (ref "U106") (pin "1") (pinfunction "Vin_1") (pintype "input"))
    )
    (net (code "38") (name "unconnected-(U101-NC-Pad5)") (class "Default")
      (node (ref "U101") (pin "5") (pinfunction "NC_5") (pintype "passive+no_connect"))
    )
    (net (code "39") (name "unconnected-(U101-NC-Pad7)") (class "Default")
      (node (ref "U101") (pin "7") (pinfunction "NC_7") (pintype "passive+no_connect"))
    )
    (net (code "40") (name "unconnected-(U106-PIO-Pad3)") (class "Default")
      (node (ref "U106") (pin "3") (pinfunction "PIO_3") (pintype "output+no_connect"))
    )
  )
)
